# Ex_EEPROM.net
KiCad netlist of a schematic drawn in EAGLE
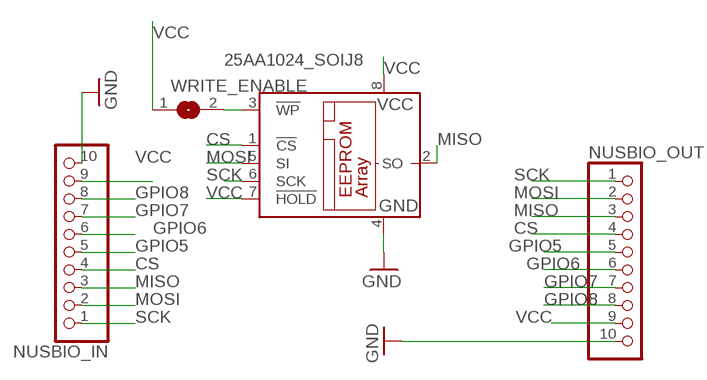
[diagram p0: schematic, sheet 1]

(export (version "E")
  (design (tool "Eeschema 10.0.6"))
  (components
    (comp (ref "25AA1024_SOIJ8")
      (value "25AA080SN")
      (footprint "eagle-import:SO-08")
      (fields (field (name "MF") "MICROCHIP") (field (name "MPN") "25AA080/SN"))
      (libsource (lib "eagle-import") (part "25SNAA080"))
    )
    (comp (ref "NUSBIO_IN")
      (value "PINHD-1X10")
      (footprint "eagle-import:1X10-BIG")
      (libsource (lib "eagle-import") (part "PINHD-1X10"))
    )
    (comp (ref "NUSBIO_OUT")
      (value "PINHD-1X10")
      (footprint "eagle-import:1X10-BIG")
      (libsource (lib "eagle-import") (part "PINHD-1X10"))
    )
    (comp (ref "WRITE_ENABLE")
      (value "SOLDERJUMPERREFLOW")
      (footprint "eagle-import:SOLDERJUMPER_REFLOW")
      (libsource (lib "eagle-import") (part "SOLDERJUMPERREFLOW"))
    )
  )
  (nets
    (net (code "1") (name "/CS") (class "Default")
      (node (ref "25AA1024_SOIJ8") (pin "1") (pinfunction "~{CS}_1") (pintype "input"))
      (node (ref "NUSBIO_IN") (pin "4") (pinfunction "4_4") (pintype "passive"))
      (node (ref "NUSBIO_OUT") (pin "4") (pinfunction "4_4") (pintype "passive"))
    )
    (net (code "2") (name "/GPIO5") (class "Default")
      (node (ref "NUSBIO_IN") (pin "5") (pinfunction "5_5") (pintype "passive"))
      (node (ref "NUSBIO_OUT") (pin "5") (pinfunction "5_5") (pintype "passive"))
    )
    (net (code "3") (name "/GPIO6") (class "Default")
      (node (ref "NUSBIO_IN") (pin "6") (pinfunction "6_6") (pintype "passive"))
      (node (ref "NUSBIO_OUT") (pin "6") (pinfunction "6_6") (pintype "passive"))
    )
    (net (code "4") (name "/GPIO7") (class "Default")
      (node (ref "NUSBIO_IN") (pin "7") (pinfunction "7_7") (pintype "passive"))
      (node (ref "NUSBIO_OUT") (pin "7") (pinfunction "7_7") (pintype "passive"))
    )
    (net (code "5") (name "/GPIO8") (class "Default")
      (node (ref "NUSBIO_IN") (pin "8") (pinfunction "8_8") (pintype "passive"))
      (node (ref "NUSBIO_OUT") (pin "8") (pinfunction "8_8") (pintype "passive"))
    )
    (net (code "6") (name "/MISO") (class "Default")
      (node (ref "25AA1024_SOIJ8") (pin "2") (pinfunction "SO_2") (pintype "bidirectional"))
      (node (ref "NUSBIO_IN") (pin "3") (pinfunction "3_3") (pintype "passive"))
      (node (ref "NUSBIO_OUT") (pin "3") (pinfunction "3_3") (pintype "passive"))
    )
    (net (code "7") (name "/MOSI") (class "Default")
      (node (ref "25AA1024_SOIJ8") (pin "5") (pinfunction "SI_5") (pintype "input"))
      (node (ref "NUSBIO_IN") (pin "2") (pinfunction "2_2") (pintype "passive"))
      (node (ref "NUSBIO_OUT") (pin "2") (pinfunction "2_2") (pintype "passive"))
    )
    (net (code "8") (name "/SCK") (class "Default")
      (node (ref "25AA1024_SOIJ8") (pin "6") (pinfunction "SCK_6") (pintype "input"))
      (node (ref "NUSBIO_IN") (pin "1") (pinfunction "1_1") (pintype "passive"))
      (node (ref "NUSBIO_OUT") (pin "1") (pinfunction "1_1") (pintype "passive"))
    )
    (net (code "9") (name "/VCC") (class "Default")
      (node (ref "25AA1024_SOIJ8") (pin "7") (pinfunction "~{HOLD}_7") (pintype "input"))
      (node (ref "25AA1024_SOIJ8") (pin "8") (pinfunction "VCC_8") (pintype "power_in"))
      (node (ref "NUSBIO_IN") (pin "9") (pinfunction "9_9") (pintype "passive"))
      (node (ref "NUSBIO_OUT") (pin "9") (pinfunction "9_9") (pintype "passive"))
      (node (ref "WRITE_ENABLE") (pin "1") (pinfunction "1_1") (pintype "passive"))
    )
    (net (code "10") (name "GND") (class "Default")
      (node (ref "25AA1024_SOIJ8") (pin "4") (pinfunction "GND_4") (pintype "power_in"))
      (node (ref "NUSBIO_IN") (pin "10") (pinfunction "10_10") (pintype "passive"))
      (node (ref "NUSBIO_OUT") (pin "10") (pinfunction "10_10") (pintype "passive"))
    )
    (net (code "11") (name "Net-(25AA1024_SOIJ8-~{WP})") (class "Default")
      (node (ref "25AA1024_SOIJ8") (pin "3") (pinfunction "~{WP}_3") (pintype "input"))
      (node (ref "WRITE_ENABLE") (pin "2") (pinfunction "2_2") (pintype "passive"))
    )
  )
)
